# Sheet1.net
KiCad netlist of a schematic drawn in Altium Designer
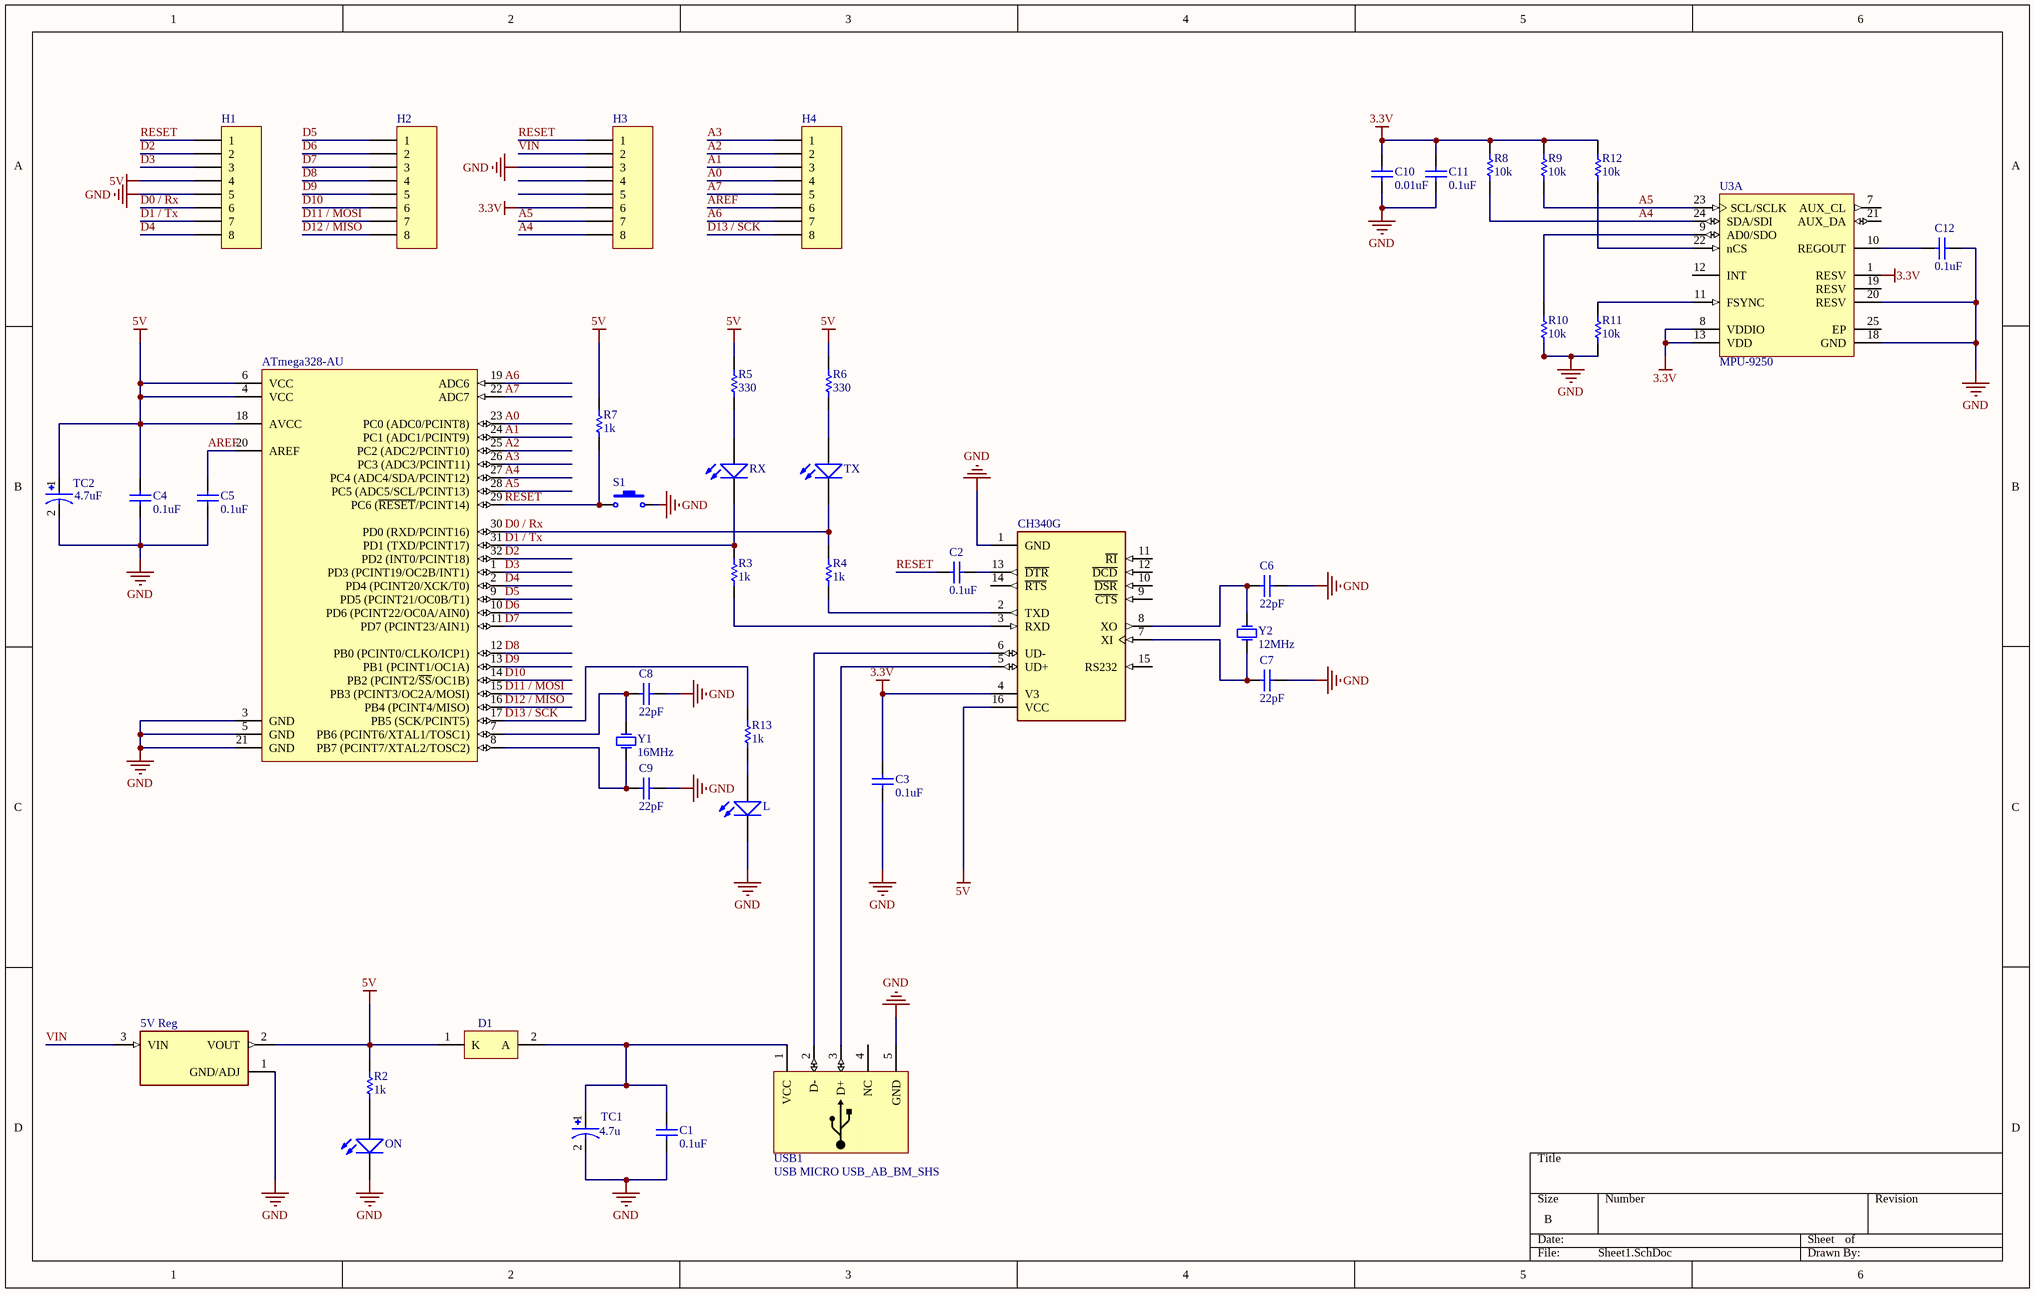
[diagram p0: Sheet1.SchDoc]

(export (version "E")
  (design (tool "Eeschema 10.0.6"))
  (components
    (comp (ref "5V Reg")
      (value "~")
      (footprint "SOT229P700X180-4N")
      (description "1A LOW DROPOUT VOLTAGE REGULATOR")
      (fields (field (name "MP") "AMS1117-5.0") (field (name "MF") "ams"))
      (libsource (lib "AMS1117-5.0") (part "AMS1117-5.0"))
    )
    (comp (ref "ATmega328-AU")
      (value "~")
      (footprint "32A_L")
      (libsource (lib "Altium Content Vault") (part "MC-8B-ATM48-SQ32"))
    )
    (comp (ref "C1")
      (value "0.1uF")
      (footprint "CAP0805")
      (description "CAP0805")
      (libsource (lib "CAP0805") (part "CAP0805"))
    )
    (comp (ref "C2")
      (value "0.1uF")
      (footprint "CAP0805")
      (description "CAP0805")
      (libsource (lib "CAP0805") (part "CAP0805"))
    )
    (comp (ref "C3")
      (value "0.1uF")
      (footprint "CAP0805")
      (description "CAP0805")
      (libsource (lib "CAP0805") (part "CAP0805"))
    )
    (comp (ref "C4")
      (value "0.1uF")
      (footprint "CAP0805")
      (description "CAP0805")
      (libsource (lib "CAP0805") (part "CAP0805"))
    )
    (comp (ref "C5")
      (value "0.1uF")
      (footprint "CAP0805")
      (description "CAP0805")
      (libsource (lib "CAP0805") (part "CAP0805"))
    )
    (comp (ref "C6")
      (value "22pF")
      (footprint "CAP0805")
      (description "CAP0805")
      (libsource (lib "CAP0805") (part "CAP0805"))
    )
    (comp (ref "C7")
      (value "22pF")
      (footprint "CAP0805")
      (description "CAP0805")
      (libsource (lib "CAP0805") (part "CAP0805"))
    )
    (comp (ref "C8")
      (value "22pF")
      (footprint "CAP0805")
      (description "CAP0805")
      (libsource (lib "CAP0805") (part "CAP0805"))
    )
    (comp (ref "C9")
      (value "22pF")
      (footprint "CAP0805")
      (description "CAP0805")
      (libsource (lib "CAP0805") (part "CAP0805"))
    )
    (comp (ref "C10")
      (value "0.01uF")
      (footprint "CAP0805")
      (description "CAP0805")
      (libsource (lib "CAP0805") (part "CAP0805"))
    )
    (comp (ref "C11")
      (value "0.1uF")
      (footprint "CAP0805")
      (description "CAP0805")
      (libsource (lib "CAP0805") (part "CAP0805"))
    )
    (comp (ref "C12")
      (value "0.1uF")
      (footprint "CAP0805")
      (description "CAP0805")
      (libsource (lib "CAP0805") (part "CAP0805"))
    )
    (comp (ref "CH340G")
      (value "~")
      (footprint "SOIC127P600X180-16N")
      (description "USB Interface Integrated Circuit")
      (fields (field (name "MP") "Ch340G") (field (name "MF") "WCH"))
      (libsource (lib "CH340G") (part "CH340G"))
    )
    (comp (ref "D1")
      (value "~")
      (footprint "ONSC-SMB-2-403A-03_V")
      (description "Schottky Power Rectifier, 2-Pin SMB, Pb-Free, Tape and Reel")
      (fields (field (name "MANUFACTURER") "On Semiconductor") (field (name "PARTNUMBER") "SS24T3G"))
      (libsource (lib "Altium Content Vault") (part "ONSC-D-K1A2-2_A"))
    )
    (comp (ref "H1") (value "~") (footprint "Header 8") (libsource (lib "Header 8") (part "Header 8")))
    (comp (ref "H2") (value "~") (footprint "Header 8") (libsource (lib "Header 8") (part "Header 8")))
    (comp (ref "H3") (value "~") (footprint "Header 8") (libsource (lib "Header 8") (part "Header 8")))
    (comp (ref "H4") (value "~") (footprint "Header 8") (libsource (lib "Header 8") (part "Header 8")))
    (comp (ref "L")
      (value "~")
      (footprint "LED_SMD_0805")
      (libsource (lib "LED_SMD_0805") (part "LED_SMD_0805"))
    )
    (comp (ref "ON")
      (value "~")
      (footprint "LED_SMD_0805")
      (libsource (lib "LED_SMD_0805") (part "LED_SMD_0805"))
    )
    (comp (ref "R2")
      (value "1k")
      (footprint "RES0805")
      (description "RES0805")
      (libsource (lib "RES0805") (part "RES0805"))
    )
    (comp (ref "R3")
      (value "1k")
      (footprint "RES0805")
      (description "RES0805")
      (libsource (lib "RES0805") (part "RES0805"))
    )
    (comp (ref "R4")
      (value "1k")
      (footprint "RES0805")
      (description "RES0805")
      (libsource (lib "RES0805") (part "RES0805"))
    )
    (comp (ref "R5")
      (value "330")
      (footprint "RES0805")
      (description "RES0805")
      (libsource (lib "RES0805") (part "RES0805"))
    )
    (comp (ref "R6")
      (value "330")
      (footprint "RES0805")
      (description "RES0805")
      (libsource (lib "RES0805") (part "RES0805"))
    )
    (comp (ref "R7")
      (value "1k")
      (footprint "RES0805")
      (description "RES0805")
      (libsource (lib "RES0805") (part "RES0805"))
    )
    (comp (ref "R8")
      (value "10k")
      (footprint "RES0805")
      (description "RES0805")
      (libsource (lib "RES0805") (part "RES0805"))
    )
    (comp (ref "R9")
      (value "10k")
      (footprint "RES0805")
      (description "RES0805")
      (libsource (lib "RES0805") (part "RES0805"))
    )
    (comp (ref "R10")
      (value "10k")
      (footprint "RES0805")
      (description "RES0805")
      (libsource (lib "RES0805") (part "RES0805"))
    )
    (comp (ref "R11")
      (value "10k")
      (footprint "RES0805")
      (description "RES0805")
      (libsource (lib "RES0805") (part "RES0805"))
    )
    (comp (ref "R12")
      (value "10k")
      (footprint "RES0805")
      (description "RES0805")
      (libsource (lib "RES0805") (part "RES0805"))
    )
    (comp (ref "R13")
      (value "1k")
      (footprint "RES0805")
      (description "RES0805")
      (libsource (lib "RES0805") (part "RES0805"))
    )
    (comp (ref "RX")
      (value "~")
      (footprint "LED_SMD_0805")
      (libsource (lib "LED_SMD_0805") (part "LED_SMD_0805"))
    )
    (comp (ref "S1")
      (value "~")
      (footprint "Push Button Switch SMD")
      (libsource (lib "Push Button Switch SMD") (part "Push Button Switch SMD"))
    )
    (comp (ref "TC1")
      (value "4.7u")
      (footprint "CAPMP3516X190N")
      (description "4.7 ÂµF Molded Tantalum Capacitors 25 V 1411 (3528 Metric), 1210 1.5Ohm")
      (fields (field (name "MP") "TAJB475K025RNJ") (field (name "MF") "AVX"))
      (libsource (lib "TAJB475K025RNJ") (part "TAJB475K025RNJ"))
    )
    (comp (ref "TC2")
      (value "4.7uF")
      (footprint "CAPMP3516X190N")
      (description "4.7 ÂµF Molded Tantalum Capacitors 25 V 1411 (3528 Metric), 1210 1.5Ohm")
      (fields (field (name "MP") "TAJB475K025RNJ") (field (name "MF") "AVX"))
      (libsource (lib "TAJB475K025RNJ") (part "TAJB475K025RNJ"))
    )
    (comp (ref "TX")
      (value "~")
      (footprint "LED_SMD_0805")
      (libsource (lib "LED_SMD_0805") (part "LED_SMD_0805"))
    )
    (comp (ref "U3")
      (value "MPU-9250")
      (footprint "INSE-QFN-24-1700X1540TP_M")
      (description "9-axis MotionTracking device, 2.4 to 3,6 V, -40 to 85 degC, 24-Pin QFN, RoHS, Tape and Reel")
      (fields (field (name "MANUFACTURER") "InvenSense"))
      (libsource (lib "Altium Content Vault") (part "INSE-MPU-9250-QFN-24"))
    )
    (comp (ref "USB1")
      (value "USB MICRO USB_AB_BM_SHS")
      (footprint "USB MICRO USB_AB_BM_SHS")
      (libsource (lib "USB MICRO USB_AB_BM_SHS") (part "USB MICRO USB_AB_BM_SHS"))
    )
    (comp (ref "Y1")
      (value "16MHz")
      (footprint "Crystal SMD")
      (description "Crystal SMD")
      (libsource (lib "Crystal SMD") (part "Crystal SMD"))
    )
    (comp (ref "Y2")
      (value "12MHz")
      (footprint "Crystal SMD")
      (description "Crystal SMD")
      (libsource (lib "Crystal SMD") (part "Crystal SMD"))
    )
  )
  (nets
    (net (code "1") (name "/A0") (class "Default")
      (node (ref "ATmega328-AU") (pin "23") (pinfunction "PC0_(ADC0/PCINT8)_23") (pintype "bidirectional"))
      (node (ref "H4") (pin "4") (pinfunction "4_4") (pintype "passive"))
    )
    (net (code "2") (name "/A1") (class "Default")
      (node (ref "ATmega328-AU") (pin "24") (pinfunction "PC1_(ADC1/PCINT9)_24") (pintype "bidirectional"))
      (node (ref "H4") (pin "3") (pinfunction "3_3") (pintype "passive"))
    )
    (net (code "3") (name "/A2") (class "Default")
      (node (ref "ATmega328-AU") (pin "25") (pinfunction "PC2_(ADC2/PCINT10)_25") (pintype "bidirectional"))
      (node (ref "H4") (pin "2") (pinfunction "2_2") (pintype "passive"))
    )
    (net (code "4") (name "/A3") (class "Default")
      (node (ref "ATmega328-AU") (pin "26") (pinfunction "PC3_(ADC3/PCINT11)_26") (pintype "bidirectional"))
      (node (ref "H4") (pin "1") (pinfunction "1_1") (pintype "passive"))
    )
    (net (code "5") (name "/A4") (class "Default")
      (node (ref "ATmega328-AU") (pin "27") (pinfunction "PC4_(ADC4/SDA/PCINT12)_27") (pintype "bidirectional"))
      (node (ref "H3") (pin "8") (pinfunction "8_8") (pintype "passive"))
      (node (ref "R8") (pin "1") (pinfunction "1_1") (pintype "passive"))
      (node (ref "U3") (pin "24") (pinfunction "SDA/SDI_24") (pintype "bidirectional"))
    )
    (net (code "6") (name "/A5") (class "Default")
      (node (ref "ATmega328-AU") (pin "28") (pinfunction "PC5_(ADC5/SCL/PCINT13)_28") (pintype "bidirectional"))
      (node (ref "H3") (pin "7") (pinfunction "7_7") (pintype "passive"))
      (node (ref "R9") (pin "1") (pinfunction "1_1") (pintype "passive"))
      (node (ref "U3") (pin "23") (pinfunction "SCL/SCLK_23") (pintype "input"))
    )
    (net (code "7") (name "/A6") (class "Default")
      (node (ref "ATmega328-AU") (pin "19") (pinfunction "ADC6_19") (pintype "input"))
      (node (ref "H4") (pin "7") (pinfunction "7_7") (pintype "passive"))
    )
    (net (code "8") (name "/A7") (class "Default")
      (node (ref "ATmega328-AU") (pin "22") (pinfunction "ADC7_22") (pintype "input"))
      (node (ref "H4") (pin "5") (pinfunction "5_5") (pintype "passive"))
    )
    (net (code "9") (name "/AREF") (class "Default")
      (node (ref "ATmega328-AU") (pin "20") (pinfunction "AREF_20") (pintype "passive"))
      (node (ref "C5") (pin "2") (pinfunction "2_2") (pintype "passive"))
      (node (ref "H4") (pin "6") (pinfunction "6_6") (pintype "passive"))
    )
    (net (code "10") (name "/D0 {slash} Rx") (class "Default")
      (node (ref "ATmega328-AU") (pin "30") (pinfunction "PD0_(RXD/PCINT16)_30") (pintype "bidirectional"))
      (node (ref "H1") (pin "6") (pinfunction "6_6") (pintype "passive"))
      (node (ref "R4") (pin "2") (pinfunction "2_2") (pintype "passive"))
      (node (ref "TX") (pin "1") (pinfunction "K_1") (pintype "passive"))
    )
    (net (code "11") (name "/D1 {slash} Tx") (class "Default")
      (node (ref "ATmega328-AU") (pin "31") (pinfunction "PD1_(TXD/PCINT17)_31") (pintype "bidirectional"))
      (node (ref "H1") (pin "7") (pinfunction "7_7") (pintype "passive"))
      (node (ref "R3") (pin "2") (pinfunction "2_2") (pintype "passive"))
      (node (ref "RX") (pin "1") (pinfunction "K_1") (pintype "passive"))
    )
    (net (code "12") (name "/D2") (class "Default")
      (node (ref "ATmega328-AU") (pin "32") (pinfunction "PD2_(INT0/PCINT18)_32") (pintype "bidirectional"))
      (node (ref "H1") (pin "2") (pinfunction "2_2") (pintype "passive"))
    )
    (net (code "13") (name "/D3") (class "Default")
      (node (ref "ATmega328-AU") (pin "1") (pinfunction "PD3_(PCINT19/OC2B/INT1)_1") (pintype "bidirectional"))
      (node (ref "H1") (pin "3") (pinfunction "3_3") (pintype "passive"))
    )
    (net (code "14") (name "/D4") (class "Default")
      (node (ref "ATmega328-AU") (pin "2") (pinfunction "PD4_(PCINT20/XCK/T0)_2") (pintype "bidirectional"))
      (node (ref "H1") (pin "8") (pinfunction "8_8") (pintype "passive"))
    )
    (net (code "15") (name "/D5") (class "Default")
      (node (ref "ATmega328-AU") (pin "9") (pinfunction "PD5_(PCINT21/OC0B/T1)_9") (pintype "bidirectional"))
      (node (ref "H2") (pin "1") (pinfunction "1_1") (pintype "passive"))
    )
    (net (code "16") (name "/D6") (class "Default")
      (node (ref "ATmega328-AU") (pin "10") (pinfunction "PD6_(PCINT22/OC0A/AIN0)_10") (pintype "bidirectional"))
      (node (ref "H2") (pin "2") (pinfunction "2_2") (pintype "passive"))
    )
    (net (code "17") (name "/D7") (class "Default")
      (node (ref "ATmega328-AU") (pin "11") (pinfunction "PD7_(PCINT23/AIN1)_11") (pintype "bidirectional"))
      (node (ref "H2") (pin "3") (pinfunction "3_3") (pintype "passive"))
    )
    (net (code "18") (name "/D8") (class "Default")
      (node (ref "ATmega328-AU") (pin "12") (pinfunction "PB0_(PCINT0/CLKO/ICP1)_12") (pintype "bidirectional"))
      (node (ref "H2") (pin "4") (pinfunction "4_4") (pintype "passive"))
    )
    (net (code "19") (name "/D9") (class "Default")
      (node (ref "ATmega328-AU") (pin "13") (pinfunction "PB1_(PCINT1/OC1A)_13") (pintype "bidirectional"))
      (node (ref "H2") (pin "5") (pinfunction "5_5") (pintype "passive"))
    )
    (net (code "20") (name "/D10") (class "Default")
      (node (ref "ATmega328-AU") (pin "14") (pinfunction "PB2_(PCINT2/~{SS}/OC1B)_14") (pintype "bidirectional"))
      (node (ref "H2") (pin "6") (pinfunction "6_6") (pintype "passive"))
    )
    (net (code "21") (name "/D11 {slash} MOSI") (class "Default")
      (node (ref "ATmega328-AU") (pin "15") (pinfunction "PB3_(PCINT3/OC2A/MOSI)_15") (pintype "bidirectional"))
      (node (ref "H2") (pin "7") (pinfunction "7_7") (pintype "passive"))
    )
    (net (code "22") (name "/D12 {slash} MISO") (class "Default")
      (node (ref "ATmega328-AU") (pin "16") (pinfunction "PB4_(PCINT4/MISO)_16") (pintype "bidirectional"))
      (node (ref "H2") (pin "8") (pinfunction "8_8") (pintype "passive"))
    )
    (net (code "23") (name "/D13 {slash} SCK") (class "Default")
      (node (ref "ATmega328-AU") (pin "17") (pinfunction "PB5_(SCK/PCINT5)_17") (pintype "bidirectional"))
      (node (ref "H4") (pin "8") (pinfunction "8_8") (pintype "passive"))
      (node (ref "R13") (pin "1") (pinfunction "1_1") (pintype "passive"))
    )
    (net (code "24") (name "/RESET") (class "Default")
      (node (ref "ATmega328-AU") (pin "29") (pinfunction "PC6_(~{RESET}/PCINT14)_29") (pintype "bidirectional"))
      (node (ref "C2") (pin "2") (pinfunction "2_2") (pintype "passive"))
      (node (ref "H1") (pin "1") (pinfunction "1_1") (pintype "passive"))
      (node (ref "H3") (pin "1") (pinfunction "1_1") (pintype "passive"))
      (node (ref "R7") (pin "1") (pinfunction "1_1") (pintype "passive"))
      (node (ref "S1") (pin "1") (pinfunction "1_1") (pintype "passive"))
    )
    (net (code "25") (name "/VIN") (class "Default")
      (node (ref "5V Reg") (pin "3") (pinfunction "VIN_3") (pintype "input"))
      (node (ref "H3") (pin "2") (pinfunction "2_2") (pintype "passive"))
    )
    (net (code "26") (name "3.3V") (class "Default")
      (node (ref "C10") (pin "2") (pinfunction "2_2") (pintype "passive"))
      (node (ref "C11") (pin "2") (pinfunction "2_2") (pintype "passive"))
      (node (ref "C3") (pin "2") (pinfunction "2_2") (pintype "passive"))
      (node (ref "CH340G") (pin "4") (pinfunction "V3_4") (pintype "power_in"))
      (node (ref "H3") (pin "6") (pinfunction "6_6") (pintype "passive"))
      (node (ref "R12") (pin "2") (pinfunction "2_2") (pintype "passive"))
      (node (ref "R8") (pin "2") (pinfunction "2_2") (pintype "passive"))
      (node (ref "R9") (pin "2") (pinfunction "2_2") (pintype "passive"))
      (node (ref "U3") (pin "1") (pinfunction "RESV_1") (pintype "power_in"))
      (node (ref "U3") (pin "13") (pinfunction "VDD_13") (pintype "power_in"))
      (node (ref "U3") (pin "8") (pinfunction "VDDIO_8") (pintype "power_in"))
    )
    (net (code "27") (name "5V") (class "Default")
      (node (ref "5V Reg") (pin "2") (pinfunction "VOUT_2") (pintype "output"))
      (node (ref "ATmega328-AU") (pin "18") (pinfunction "AVCC_18") (pintype "power_in"))
      (node (ref "ATmega328-AU") (pin "4") (pinfunction "VCC_4") (pintype "power_in"))
      (node (ref "ATmega328-AU") (pin "6") (pinfunction "VCC_6") (pintype "power_in"))
      (node (ref "C4") (pin "1") (pinfunction "1_1") (pintype "passive"))
      (node (ref "CH340G") (pin "16") (pinfunction "VCC_16") (pintype "power_in"))
      (node (ref "D1") (pin "1") (pinfunction "K_1") (pintype "passive"))
      (node (ref "H1") (pin "4") (pinfunction "4_4") (pintype "passive"))
      (node (ref "R2") (pin "2") (pinfunction "2_2") (pintype "passive"))
      (node (ref "R5") (pin "2") (pinfunction "2_2") (pintype "passive"))
      (node (ref "R6") (pin "2") (pinfunction "2_2") (pintype "passive"))
      (node (ref "R7") (pin "2") (pinfunction "2_2") (pintype "passive"))
      (node (ref "TC2") (pin "1") (pinfunction "1_1") (pintype "passive"))
    )
    (net (code "28") (name "GND") (class "Default")
      (node (ref "5V Reg") (pin "1") (pinfunction "GND/ADJ_1") (pintype "power_in"))
      (node (ref "ATmega328-AU") (pin "21") (pinfunction "GND_21") (pintype "power_in"))
      (node (ref "ATmega328-AU") (pin "3") (pinfunction "GND_3") (pintype "power_in"))
      (node (ref "ATmega328-AU") (pin "5") (pinfunction "GND_5") (pintype "power_in"))
      (node (ref "C1") (pin "1") (pinfunction "1_1") (pintype "passive"))
      (node (ref "C10") (pin "1") (pinfunction "1_1") (pintype "passive"))
      (node (ref "C11") (pin "1") (pinfunction "1_1") (pintype "passive"))
      (node (ref "C12") (pin "2") (pinfunction "2_2") (pintype "passive"))
      (node (ref "C3") (pin "1") (pinfunction "1_1") (pintype "passive"))
      (node (ref "C4") (pin "2") (pinfunction "2_2") (pintype "passive"))
      (node (ref "C5") (pin "1") (pinfunction "1_1") (pintype "passive"))
      (node (ref "C6") (pin "1") (pinfunction "1_1") (pintype "passive"))
      (node (ref "C7") (pin "1") (pinfunction "1_1") (pintype "passive"))
      (node (ref "C8") (pin "1") (pinfunction "1_1") (pintype "passive"))
      (node (ref "C9") (pin "1") (pinfunction "1_1") (pintype "passive"))
      (node (ref "CH340G") (pin "1") (pinfunction "GND_1") (pintype "power_in"))
      (node (ref "H1") (pin "5") (pinfunction "5_5") (pintype "passive"))
      (node (ref "H3") (pin "3") (pinfunction "3_3") (pintype "passive"))
      (node (ref "L") (pin "1") (pinfunction "K_1") (pintype "passive"))
      (node (ref "ON") (pin "1") (pinfunction "K_1") (pintype "passive"))
      (node (ref "R10") (pin "2") (pinfunction "2_2") (pintype "passive"))
      (node (ref "R11") (pin "1") (pinfunction "1_1") (pintype "passive"))
      (node (ref "S1") (pin "2") (pinfunction "2_2") (pintype "passive"))
      (node (ref "TC1") (pin "2") (pinfunction "2_2") (pintype "passive"))
      (node (ref "TC2") (pin "2") (pinfunction "2_2") (pintype "passive"))
      (node (ref "U3") (pin "18") (pinfunction "GND_18") (pintype "power_in"))
      (node (ref "U3") (pin "20") (pinfunction "RESV_20") (pintype "power_in"))
      (node (ref "USB1") (pin "5") (pinfunction "GND_5") (pintype "power_in"))
    )
    (net (code "29") (name "Net-(ATmega328-AU-PB6_(PCINT6{slash}XTAL1{slash}TOSC1))") (class "Default")
      (node (ref "ATmega328-AU") (pin "7") (pinfunction "PB6_(PCINT6/XTAL1/TOSC1)_7") (pintype "bidirectional"))
      (node (ref "C8") (pin "2") (pinfunction "2_2") (pintype "passive"))
      (node (ref "Y1") (pin "2") (pinfunction "OSC2_2") (pintype "passive"))
    )
    (net (code "30") (name "Net-(ATmega328-AU-PB7_(PCINT7{slash}XTAL2{slash}TOSC2))") (class "Default")
      (node (ref "ATmega328-AU") (pin "8") (pinfunction "PB7_(PCINT7/XTAL2/TOSC2)_8") (pintype "bidirectional"))
      (node (ref "C9") (pin "2") (pinfunction "2_2") (pintype "passive"))
      (node (ref "Y1") (pin "1") (pinfunction "OSC1_1") (pintype "passive"))
    )
    (net (code "31") (name "Net-(CH340G-RXD)") (class "Default")
      (node (ref "CH340G") (pin "3") (pinfunction "RXD_3") (pintype "input"))
      (node (ref "R3") (pin "1") (pinfunction "1_1") (pintype "passive"))
    )
    (net (code "32") (name "Net-(CH340G-TXD)") (class "Default")
      (node (ref "CH340G") (pin "2") (pinfunction "TXD_2") (pintype "output"))
      (node (ref "R4") (pin "1") (pinfunction "1_1") (pintype "passive"))
    )
    (net (code "33") (name "Net-(CH340G-UD+)") (class "Default")
      (node (ref "CH340G") (pin "5") (pinfunction "UD+_5") (pintype "bidirectional"))
      (node (ref "USB1") (pin "3") (pinfunction "D+_3") (pintype "bidirectional"))
    )
    (net (code "34") (name "Net-(CH340G-UD-)") (class "Default")
      (node (ref "CH340G") (pin "6") (pinfunction "UD-_6") (pintype "bidirectional"))
      (node (ref "USB1") (pin "2") (pinfunction "D-_2") (pintype "bidirectional"))
    )
    (net (code "35") (name "Net-(CH340G-XI)") (class "Default")
      (node (ref "C7") (pin "2") (pinfunction "2_2") (pintype "passive"))
      (node (ref "CH340G") (pin "7") (pinfunction "XI_7") (pintype "input"))
      (node (ref "Y2") (pin "1") (pinfunction "OSC1_1") (pintype "passive"))
    )
    (net (code "36") (name "Net-(CH340G-XO)") (class "Default")
      (node (ref "C6") (pin "2") (pinfunction "2_2") (pintype "passive"))
      (node (ref "CH340G") (pin "8") (pinfunction "XO_8") (pintype "output"))
      (node (ref "Y2") (pin "2") (pinfunction "OSC2_2") (pintype "passive"))
    )
    (net (code "37") (name "Net-(CH340G-~{DTR})") (class "Default")
      (node (ref "C2") (pin "1") (pinfunction "1_1") (pintype "passive"))
      (node (ref "CH340G") (pin "13") (pinfunction "~{DTR}_13") (pintype "output"))
    )
    (net (code "38") (name "Net-(D1-A)") (class "Default")
      (node (ref "C1") (pin "2") (pinfunction "2_2") (pintype "passive"))
      (node (ref "D1") (pin "2") (pinfunction "A_2") (pintype "passive"))
      (node (ref "TC1") (pin "1") (pinfunction "1_1") (pintype "passive"))
      (node (ref "USB1") (pin "1") (pinfunction "VCC_1") (pintype "power_in"))
    )
    (net (code "39") (name "Net-(L-A)") (class "Default")
      (node (ref "L") (pin "2") (pinfunction "A_2") (pintype "passive"))
      (node (ref "R13") (pin "2") (pinfunction "2_2") (pintype "passive"))
    )
    (net (code "40") (name "Net-(ON-A)") (class "Default")
      (node (ref "ON") (pin "2") (pinfunction "A_2") (pintype "passive"))
      (node (ref "R2") (pin "1") (pinfunction "1_1") (pintype "passive"))
    )
    (net (code "41") (name "Net-(RX-A)") (class "Default")
      (node (ref "R5") (pin "1") (pinfunction "1_1") (pintype "passive"))
      (node (ref "RX") (pin "2") (pinfunction "A_2") (pintype "passive"))
    )
    (net (code "42") (name "Net-(TX-A)") (class "Default")
      (node (ref "R6") (pin "1") (pinfunction "1_1") (pintype "passive"))
      (node (ref "TX") (pin "2") (pinfunction "A_2") (pintype "passive"))
    )
    (net (code "43") (name "Net-(U3A-AD0{slash}SDO)") (class "Default")
      (node (ref "R10") (pin "1") (pinfunction "1_1") (pintype "passive"))
      (node (ref "U3") (pin "9") (pinfunction "AD0/SDO_9") (pintype "bidirectional"))
    )
    (net (code "44") (name "Net-(U3A-FSYNC)") (class "Default")
      (node (ref "R11") (pin "2") (pinfunction "2_2") (pintype "passive"))
      (node (ref "U3") (pin "11") (pinfunction "FSYNC_11") (pintype "input"))
    )
    (net (code "45") (name "Net-(U3A-REGOUT)") (class "Default")
      (node (ref "C12") (pin "1") (pinfunction "1_1") (pintype "passive"))
      (node (ref "U3") (pin "10") (pinfunction "REGOUT_10") (pintype "passive"))
    )
    (net (code "46") (name "Net-(U3A-nCS)") (class "Default")
      (node (ref "R12") (pin "1") (pinfunction "1_1") (pintype "passive"))
      (node (ref "U3") (pin "22") (pinfunction "nCS_22") (pintype "input"))
    )
    (net (code "47") (name "unconnected-(CH340G-RS232-Pad15)") (class "Default")
      (node (ref "CH340G") (pin "15") (pinfunction "RS232_15") (pintype "input"))
    )
    (net (code "48") (name "unconnected-(CH340G-~{CTS}-Pad9)") (class "Default")
      (node (ref "CH340G") (pin "9") (pinfunction "~{CTS}_9") (pintype "input"))
    )
    (net (code "49") (name "unconnected-(CH340G-~{DCD}-Pad12)") (class "Default")
      (node (ref "CH340G") (pin "12") (pinfunction "~{DCD}_12") (pintype "input"))
    )
    (net (code "50") (name "unconnected-(CH340G-~{DSR}-Pad10)") (class "Default")
      (node (ref "CH340G") (pin "10") (pinfunction "~{DSR}_10") (pintype "input"))
    )
    (net (code "51") (name "unconnected-(CH340G-~{RI}-Pad11)") (class "Default")
      (node (ref "CH340G") (pin "11") (pinfunction "~{RI}_11") (pintype "input"))
    )
    (net (code "52") (name "unconnected-(CH340G-~{RTS}-Pad14)") (class "Default")
      (node (ref "CH340G") (pin "14") (pinfunction "~{RTS}_14") (pintype "output"))
    )
    (net (code "53") (name "unconnected-(H3-Pad4)") (class "Default")
      (node (ref "H3") (pin "4") (pinfunction "4_4") (pintype "passive"))
    )
    (net (code "54") (name "unconnected-(H3-Pad5)") (class "Default")
      (node (ref "H3") (pin "5") (pinfunction "5_5") (pintype "passive"))
    )
    (net (code "55") (name "unconnected-(U3A-AUX_CL-Pad7)") (class "Default")
      (node (ref "U3") (pin "7") (pinfunction "AUX_CL_7") (pintype "output"))
    )
    (net (code "56") (name "unconnected-(U3A-AUX_DA-Pad21)") (class "Default")
      (node (ref "U3") (pin "21") (pinfunction "AUX_DA_21") (pintype "bidirectional"))
    )
    (net (code "57") (name "unconnected-(U3A-EP-Pad25)") (class "Default")
      (node (ref "U3") (pin "25") (pinfunction "EP_25") (pintype "passive"))
    )
    (net (code "58") (name "unconnected-(U3A-INT-Pad12)") (class "Default")
      (node (ref "U3") (pin "12") (pinfunction "INT_12") (pintype "tri_state"))
    )
    (net (code "59") (name "unconnected-(U3A-RESV-Pad19)") (class "Default")
      (node (ref "U3") (pin "19") (pinfunction "RESV_19") (pintype "passive"))
    )
    (net (code "60") (name "unconnected-(USB1-NC-Pad4)") (class "Default")
      (node (ref "USB1") (pin "4") (pinfunction "NC_4") (pintype "passive"))
    )
  )
)
